# ATRACK_Dongle_V1.net
KiCad netlist of a schematic drawn in Altium Designer
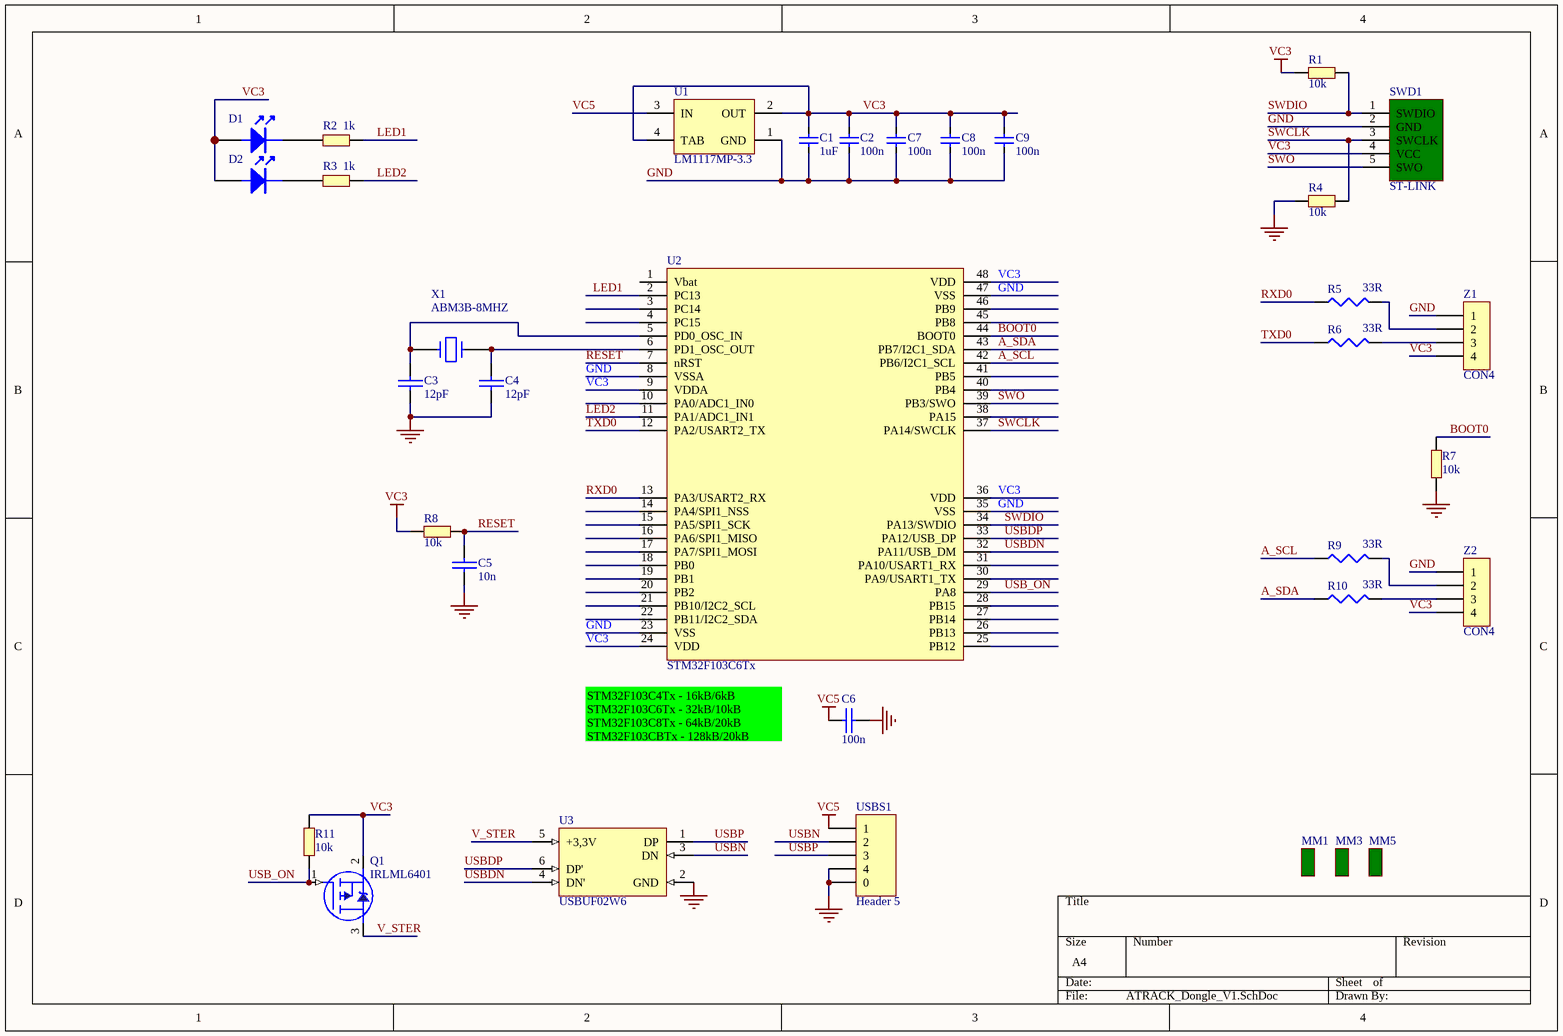
[diagram p0: ATRACK_Dongle_V1.SchDoc]

(export (version "E")
  (design (tool "Eeschema 10.0.6"))
  (components
    (comp (ref "C1") (value "1uF") (footprint "0603C") (libsource (lib "*") (part "CAP")))
    (comp (ref "C2") (value "100n") (footprint "0603C") (libsource (lib "*") (part "CAP")))
    (comp (ref "C3")
      (value "12pF")
      (footprint "0603C")
      (description "Capacitor")
      (libsource (lib "") (part "CAP_1"))
    )
    (comp (ref "C4")
      (value "12pF")
      (footprint "0603C")
      (description "Capacitor")
      (libsource (lib "") (part "CAP_1"))
    )
    (comp (ref "C5")
      (value "10n")
      (footprint "0603C")
      (description "Capacitor")
      (libsource (lib "") (part "CAP_1"))
    )
    (comp (ref "C6")
      (value "100n")
      (footprint "0603C")
      (description "Capacitor")
      (libsource (lib "") (part "CAP_1"))
    )
    (comp (ref "C7") (value "100n") (footprint "0603C") (libsource (lib "*") (part "CAP")))
    (comp (ref "C8") (value "100n") (footprint "0603C") (libsource (lib "*") (part "CAP")))
    (comp (ref "C9") (value "100n") (footprint "0603C") (libsource (lib "*") (part "CAP")))
    (comp (ref "D1") (value "~") (footprint "0603LG") (libsource (lib "*") (part "LED")))
    (comp (ref "D2") (value "~") (footprint "0603LR") (libsource (lib "*") (part "LED")))
    (comp (ref "MM1") (value "~") (footprint "REF_CIR") (libsource (lib "*") (part "MECH")))
    (comp (ref "MM3") (value "~") (footprint "REF_SQR") (libsource (lib "*") (part "MECH")))
    (comp (ref "MM5") (value "~") (footprint "PB_FREE_GRAF") (libsource (lib "*") (part "MECH")))
    (comp (ref "Q1")
      (value "IRLML6401")
      (footprint "SOT23")
      (description "Low Charge N-Channel MOSFET")
      (libsource (lib "*") (part "IRLML9303"))
    )
    (comp (ref "R1") (value "10k") (footprint "0603R") (libsource (lib "") (part "RES3_1")))
    (comp (ref "R2") (value "1k") (footprint "0603R") (libsource (lib "") (part "RES3_1")))
    (comp (ref "R3") (value "1k") (footprint "0603R") (libsource (lib "") (part "RES3_1")))
    (comp (ref "R4") (value "10k") (footprint "0603R") (libsource (lib "") (part "RES3_1")))
    (comp (ref "R5") (value "33R") (footprint "0603R") (libsource (lib "*") (part "RES1")))
    (comp (ref "R6") (value "33R") (footprint "0603R") (libsource (lib "*") (part "RES1")))
    (comp (ref "R7") (value "10k") (footprint "0603R") (libsource (lib "*") (part "RES3")))
    (comp (ref "R8") (value "10k") (footprint "0603R") (libsource (lib "") (part "RES3_1")))
    (comp (ref "R9") (value "33R") (footprint "0603R") (libsource (lib "*") (part "RES1")))
    (comp (ref "R10") (value "33R") (footprint "0603R") (libsource (lib "*") (part "RES1")))
    (comp (ref "R11") (value "10k") (footprint "0603R") (libsource (lib "") (part "RES3_2")))
    (comp (ref "SWD1")
      (value "ST-LINK")
      (footprint "PIN5_SWD")
      (description "Header, 4-Pin")
      (fields (field (name "PUBLISHER") "Altium Limited"))
      (libsource (lib "GkSchlib") (part "SW5_CON"))
    )
    (comp (ref "U1")
      (value "LM1117MP-3.3")
      (footprint "MP04A_N1")
      (description "800mA Low-Dropout Linear Regulator")
      (fields
        (field (name "MANUFACTURER") "National Semiconductor")
        (field (name "DIGIKEYPARTNUMBER") "LM1117MP-3.3CT-ND")
        (field (name "PUBLISHER") "Altium Limited")
      )
      (libsource (lib "NSC LDO") (part "LM1117MP-3.3"))
    )
    (comp (ref "U2")
      (value "STM32F103C6Tx")
      (footprint "LQFP48")
      (description "STM32F103CxTx")
      (libsource (lib "GkSchlib") (part "STM32F103_LQFP48"))
    )
    (comp (ref "U3") (value "USBUF02W6") (footprint "SOT323-6L") (libsource (lib "*") (part "USBUF01W6")))
    (comp (ref "USBS1")
      (value "Header 5")
      (footprint "USB_KR")
      (description "Header, 5-Pin")
      (fields (field (name "PUBLISHER") "Altium Limited"))
      (libsource (lib "Miscellaneous Connectors") (part "Header 5"))
    )
    (comp (ref "X1")
      (value "ABM3B-8MHZ")
      (footprint "XTAL3")
      (description "Crystal")
      (libsource (lib "*") (part "CRYSTAL"))
    )
    (comp (ref "Z1")
      (value "CON4")
      (footprint "PIN4")
      (description "Connector")
      (libsource (lib "*") (part "CON4"))
    )
    (comp (ref "Z2")
      (value "CON4")
      (footprint "PIN4")
      (description "Connector")
      (libsource (lib "*") (part "CON4"))
    )
  )
  (nets
    (net (code "1") (name "/A_SCL") (class "Default")
      (node (ref "R9") (pin "2") (pinfunction "2_2") (pintype "passive"))
      (node (ref "U2") (pin "42") (pinfunction "PB6/I2C1_SCL_42") (pintype "passive"))
    )
    (net (code "2") (name "/A_SDA") (class "Default")
      (node (ref "R10") (pin "2") (pinfunction "2_2") (pintype "passive"))
      (node (ref "U2") (pin "43") (pinfunction "PB7/I2C1_SDA_43") (pintype "passive"))
    )
    (net (code "3") (name "/BOOT0") (class "Default")
      (node (ref "R7") (pin "1") (pintype "passive"))
      (node (ref "U2") (pin "44") (pinfunction "BOOT0_44") (pintype "passive"))
    )
    (net (code "4") (name "/LED1") (class "Default")
      (node (ref "R2") (pin "2") (pintype "passive"))
      (node (ref "U2") (pin "2") (pinfunction "PC13_2") (pintype "passive"))
    )
    (net (code "5") (name "/LED2") (class "Default")
      (node (ref "R3") (pin "2") (pintype "passive"))
      (node (ref "U2") (pin "11") (pinfunction "PA1/ADC1_IN1_11") (pintype "passive"))
    )
    (net (code "6") (name "/RESET") (class "Default")
      (node (ref "C5") (pin "1") (pinfunction "1_1") (pintype "passive"))
      (node (ref "R8") (pin "2") (pintype "passive"))
      (node (ref "U2") (pin "7") (pinfunction "nRST_7") (pintype "passive"))
    )
    (net (code "7") (name "/RXD0") (class "Default")
      (node (ref "R5") (pin "2") (pinfunction "2_2") (pintype "passive"))
      (node (ref "U2") (pin "13") (pinfunction "PA3/USART2_RX_13") (pintype "passive"))
    )
    (net (code "8") (name "/SWCLK") (class "Default")
      (node (ref "R4") (pin "2") (pintype "passive"))
      (node (ref "SWD1") (pin "3") (pinfunction "SWCLK_3") (pintype "passive"))
      (node (ref "U2") (pin "37") (pinfunction "PA14/SWCLK_37") (pintype "passive"))
    )
    (net (code "9") (name "/SWDIO") (class "Default")
      (node (ref "R1") (pin "2") (pintype "passive"))
      (node (ref "SWD1") (pin "1") (pinfunction "SWDIO_1") (pintype "passive"))
      (node (ref "U2") (pin "34") (pinfunction "PA13/SWDIO_34") (pintype "passive"))
    )
    (net (code "10") (name "/SWO") (class "Default")
      (node (ref "SWD1") (pin "5") (pinfunction "SWO_5") (pintype "passive"))
      (node (ref "U2") (pin "39") (pinfunction "PB3/SWO_39") (pintype "passive"))
    )
    (net (code "11") (name "/TXD0") (class "Default")
      (node (ref "R6") (pin "2") (pinfunction "2_2") (pintype "passive"))
      (node (ref "U2") (pin "12") (pinfunction "PA2/USART2_TX_12") (pintype "passive"))
    )
    (net (code "12") (name "/USBDN") (class "Default")
      (node (ref "U2") (pin "32") (pinfunction "PA11/USB_DM_32") (pintype "passive"))
      (node (ref "U3") (pin "4") (pinfunction "DN'_4") (pintype "input"))
    )
    (net (code "13") (name "/USBDP") (class "Default")
      (node (ref "U2") (pin "33") (pinfunction "PA12/USB_DP_33") (pintype "passive"))
      (node (ref "U3") (pin "6") (pinfunction "DP'_6") (pintype "input"))
    )
    (net (code "14") (name "/USBN") (class "Default")
      (node (ref "U3") (pin "3") (pinfunction "DN_3") (pintype "input"))
      (node (ref "USBS1") (pin "2") (pinfunction "2_2") (pintype "passive"))
    )
    (net (code "15") (name "/USBP") (class "Default")
      (node (ref "U3") (pin "1") (pinfunction "DP_1") (pintype "passive"))
      (node (ref "USBS1") (pin "3") (pinfunction "3_3") (pintype "passive"))
    )
    (net (code "16") (name "/USB_ON") (class "Default")
      (node (ref "Q1") (pin "1") (pinfunction "GATE_1") (pintype "input"))
      (node (ref "R11") (pin "1") (pintype "passive"))
      (node (ref "U2") (pin "29") (pinfunction "PA8_29") (pintype "passive"))
    )
    (net (code "17") (name "/V_STER") (class "Default")
      (node (ref "Q1") (pin "3") (pinfunction "DRAIN_3") (pintype "passive"))
      (node (ref "U3") (pin "5") (pinfunction "+3,3V_5") (pintype "input"))
    )
    (net (code "18") (name "GND") (class "Default")
      (node (ref "C1") (pin "2") (pintype "passive"))
      (node (ref "C2") (pin "2") (pintype "passive"))
      (node (ref "C3") (pin "2") (pinfunction "2_2") (pintype "passive"))
      (node (ref "C4") (pin "2") (pinfunction "2_2") (pintype "passive"))
      (node (ref "C5") (pin "2") (pinfunction "2_2") (pintype "passive"))
      (node (ref "C6") (pin "2") (pinfunction "2_2") (pintype "passive"))
      (node (ref "C7") (pin "2") (pintype "passive"))
      (node (ref "C8") (pin "2") (pintype "passive"))
      (node (ref "C9") (pin "2") (pintype "passive"))
      (node (ref "R4") (pin "1") (pintype "passive"))
      (node (ref "R7") (pin "2") (pintype "passive"))
      (node (ref "SWD1") (pin "2") (pinfunction "GND_2") (pintype "passive"))
      (node (ref "U1") (pin "1") (pinfunction "GND_1") (pintype "power_in"))
      (node (ref "U2") (pin "23") (pinfunction "VSS_23") (pintype "passive"))
      (node (ref "U2") (pin "35") (pinfunction "VSS_35") (pintype "passive"))
      (node (ref "U2") (pin "47") (pinfunction "VSS_47") (pintype "passive"))
      (node (ref "U2") (pin "8") (pinfunction "VSSA_8") (pintype "passive"))
      (node (ref "U3") (pin "2") (pinfunction "GND_2") (pintype "input"))
      (node (ref "USBS1") (pin "0") (pinfunction "0_0") (pintype "passive"))
      (node (ref "USBS1") (pin "4") (pinfunction "4_4") (pintype "passive"))
      (node (ref "Z1") (pin "1") (pinfunction "1_1") (pintype "passive"))
      (node (ref "Z2") (pin "1") (pinfunction "1_1") (pintype "passive"))
    )
    (net (code "19") (name "Net-(D1-2)") (class "Default")
      (node (ref "D1") (pin "K") (pinfunction "2_K") (pintype "passive"))
      (node (ref "R2") (pin "1") (pintype "passive"))
    )
    (net (code "20") (name "Net-(D2-2)") (class "Default")
      (node (ref "D2") (pin "K") (pinfunction "2_K") (pintype "passive"))
      (node (ref "R3") (pin "1") (pintype "passive"))
    )
    (net (code "21") (name "Net-(R5-Pad1)") (class "Default")
      (node (ref "R5") (pin "1") (pinfunction "1_1") (pintype "passive"))
      (node (ref "Z1") (pin "2") (pinfunction "2_2") (pintype "passive"))
    )
    (net (code "22") (name "Net-(R6-Pad1)") (class "Default")
      (node (ref "R6") (pin "1") (pinfunction "1_1") (pintype "passive"))
      (node (ref "Z1") (pin "3") (pinfunction "3_3") (pintype "passive"))
    )
    (net (code "23") (name "Net-(R9-Pad1)") (class "Default")
      (node (ref "R9") (pin "1") (pinfunction "1_1") (pintype "passive"))
      (node (ref "Z2") (pin "2") (pinfunction "2_2") (pintype "passive"))
    )
    (net (code "24") (name "Net-(R10-Pad1)") (class "Default")
      (node (ref "R10") (pin "1") (pinfunction "1_1") (pintype "passive"))
      (node (ref "Z2") (pin "3") (pinfunction "3_3") (pintype "passive"))
    )
    (net (code "25") (name "Net-(U2-PD0_OSC_IN)") (class "Default")
      (node (ref "C3") (pin "1") (pinfunction "1_1") (pintype "passive"))
      (node (ref "U2") (pin "5") (pinfunction "PD0_OSC_IN_5") (pintype "passive"))
      (node (ref "X1") (pin "1") (pinfunction "1_1") (pintype "passive"))
    )
    (net (code "26") (name "Net-(U2-PD1_OSC_OUT)") (class "Default")
      (node (ref "C4") (pin "1") (pinfunction "1_1") (pintype "passive"))
      (node (ref "U2") (pin "6") (pinfunction "PD1_OSC_OUT_6") (pintype "passive"))
      (node (ref "X1") (pin "3") (pinfunction "2_3") (pintype "passive"))
    )
    (net (code "27") (name "VC3") (class "Default")
      (node (ref "C1") (pin "1") (pintype "passive"))
      (node (ref "C2") (pin "1") (pintype "passive"))
      (node (ref "C7") (pin "1") (pintype "passive"))
      (node (ref "C8") (pin "1") (pintype "passive"))
      (node (ref "C9") (pin "1") (pintype "passive"))
      (node (ref "D1") (pin "A") (pinfunction "1_A") (pintype "passive"))
      (node (ref "D2") (pin "A") (pinfunction "1_A") (pintype "passive"))
      (node (ref "Q1") (pin "2") (pinfunction "SOURCE_2") (pintype "passive"))
      (node (ref "R1") (pin "1") (pintype "passive"))
      (node (ref "R11") (pin "2") (pintype "passive"))
      (node (ref "R8") (pin "1") (pintype "passive"))
      (node (ref "SWD1") (pin "4") (pinfunction "VCC_4") (pintype "passive"))
      (node (ref "U1") (pin "2") (pinfunction "OUT_2") (pintype "power_in"))
      (node (ref "U1") (pin "4") (pinfunction "TAB_4") (pintype "power_in"))
      (node (ref "U2") (pin "24") (pinfunction "VDD_24") (pintype "passive"))
      (node (ref "U2") (pin "36") (pinfunction "VDD_36") (pintype "passive"))
      (node (ref "U2") (pin "48") (pinfunction "VDD_48") (pintype "passive"))
      (node (ref "U2") (pin "9") (pinfunction "VDDA_9") (pintype "passive"))
      (node (ref "Z1") (pin "4") (pinfunction "4_4") (pintype "passive"))
      (node (ref "Z2") (pin "4") (pinfunction "4_4") (pintype "passive"))
    )
    (net (code "28") (name "VC5") (class "Default")
      (node (ref "C6") (pin "1") (pinfunction "1_1") (pintype "passive"))
      (node (ref "U1") (pin "3") (pinfunction "IN_3") (pintype "power_in"))
      (node (ref "USBS1") (pin "1") (pinfunction "1_1") (pintype "passive"))
    )
    (net (code "29") (name "unconnected-(U2-PA0{slash}ADC1_IN0-Pad10)") (class "Default")
      (node (ref "U2") (pin "10") (pinfunction "PA0/ADC1_IN0_10") (pintype "passive"))
    )
    (net (code "30") (name "unconnected-(U2-PA4{slash}SPI1_NSS-Pad14)") (class "Default")
      (node (ref "U2") (pin "14") (pinfunction "PA4/SPI1_NSS_14") (pintype "passive"))
    )
    (net (code "31") (name "unconnected-(U2-PA5{slash}SPI1_SCK-Pad15)") (class "Default")
      (node (ref "U2") (pin "15") (pinfunction "PA5/SPI1_SCK_15") (pintype "passive"))
    )
    (net (code "32") (name "unconnected-(U2-PA6{slash}SPI1_MISO-Pad16)") (class "Default")
      (node (ref "U2") (pin "16") (pinfunction "PA6/SPI1_MISO_16") (pintype "passive"))
    )
    (net (code "33") (name "unconnected-(U2-PA7{slash}SPI1_MOSI-Pad17)") (class "Default")
      (node (ref "U2") (pin "17") (pinfunction "PA7/SPI1_MOSI_17") (pintype "passive"))
    )
    (net (code "34") (name "unconnected-(U2-PA9{slash}USART1_TX-Pad30)") (class "Default")
      (node (ref "U2") (pin "30") (pinfunction "PA9/USART1_TX_30") (pintype "passive"))
    )
    (net (code "35") (name "unconnected-(U2-PA10{slash}USART1_RX-Pad31)") (class "Default")
      (node (ref "U2") (pin "31") (pinfunction "PA10/USART1_RX_31") (pintype "passive"))
    )
    (net (code "36") (name "unconnected-(U2-PA15-Pad38)") (class "Default")
      (node (ref "U2") (pin "38") (pinfunction "PA15_38") (pintype "passive"))
    )
    (net (code "37") (name "unconnected-(U2-PB0-Pad18)") (class "Default")
      (node (ref "U2") (pin "18") (pinfunction "PB0_18") (pintype "passive"))
    )
    (net (code "38") (name "unconnected-(U2-PB1-Pad19)") (class "Default")
      (node (ref "U2") (pin "19") (pinfunction "PB1_19") (pintype "passive"))
    )
    (net (code "39") (name "unconnected-(U2-PB2-Pad20)") (class "Default")
      (node (ref "U2") (pin "20") (pinfunction "PB2_20") (pintype "passive"))
    )
    (net (code "40") (name "unconnected-(U2-PB4-Pad40)") (class "Default")
      (node (ref "U2") (pin "40") (pinfunction "PB4_40") (pintype "passive"))
    )
    (net (code "41") (name "unconnected-(U2-PB5-Pad41)") (class "Default")
      (node (ref "U2") (pin "41") (pinfunction "PB5_41") (pintype "passive"))
    )
    (net (code "42") (name "unconnected-(U2-PB8-Pad45)") (class "Default")
      (node (ref "U2") (pin "45") (pinfunction "PB8_45") (pintype "passive"))
    )
    (net (code "43") (name "unconnected-(U2-PB9-Pad46)") (class "Default")
      (node (ref "U2") (pin "46") (pinfunction "PB9_46") (pintype "passive"))
    )
    (net (code "44") (name "unconnected-(U2-PB10{slash}I2C2_SCL-Pad21)") (class "Default")
      (node (ref "U2") (pin "21") (pinfunction "PB10/I2C2_SCL_21") (pintype "passive"))
    )
    (net (code "45") (name "unconnected-(U2-PB11{slash}I2C2_SDA-Pad22)") (class "Default")
      (node (ref "U2") (pin "22") (pinfunction "PB11/I2C2_SDA_22") (pintype "passive"))
    )
    (net (code "46") (name "unconnected-(U2-PB12-Pad25)") (class "Default")
      (node (ref "U2") (pin "25") (pinfunction "PB12_25") (pintype "passive"))
    )
    (net (code "47") (name "unconnected-(U2-PB13-Pad26)") (class "Default")
      (node (ref "U2") (pin "26") (pinfunction "PB13_26") (pintype "passive"))
    )
    (net (code "48") (name "unconnected-(U2-PB14-Pad27)") (class "Default")
      (node (ref "U2") (pin "27") (pinfunction "PB14_27") (pintype "passive"))
    )
    (net (code "49") (name "unconnected-(U2-PB15-Pad28)") (class "Default")
      (node (ref "U2") (pin "28") (pinfunction "PB15_28") (pintype "passive"))
    )
    (net (code "50") (name "unconnected-(U2-PC14-Pad3)") (class "Default")
      (node (ref "U2") (pin "3") (pinfunction "PC14_3") (pintype "passive"))
    )
    (net (code "51") (name "unconnected-(U2-PC15-Pad4)") (class "Default")
      (node (ref "U2") (pin "4") (pinfunction "PC15_4") (pintype "passive"))
    )
    (net (code "52") (name "unconnected-(U2-Vbat-Pad1)") (class "Default")
      (node (ref "U2") (pin "1") (pinfunction "Vbat_1") (pintype "passive"))
    )
  )
)
